# ATDevBoard.net
KiCad netlist of a schematic drawn in EAGLE
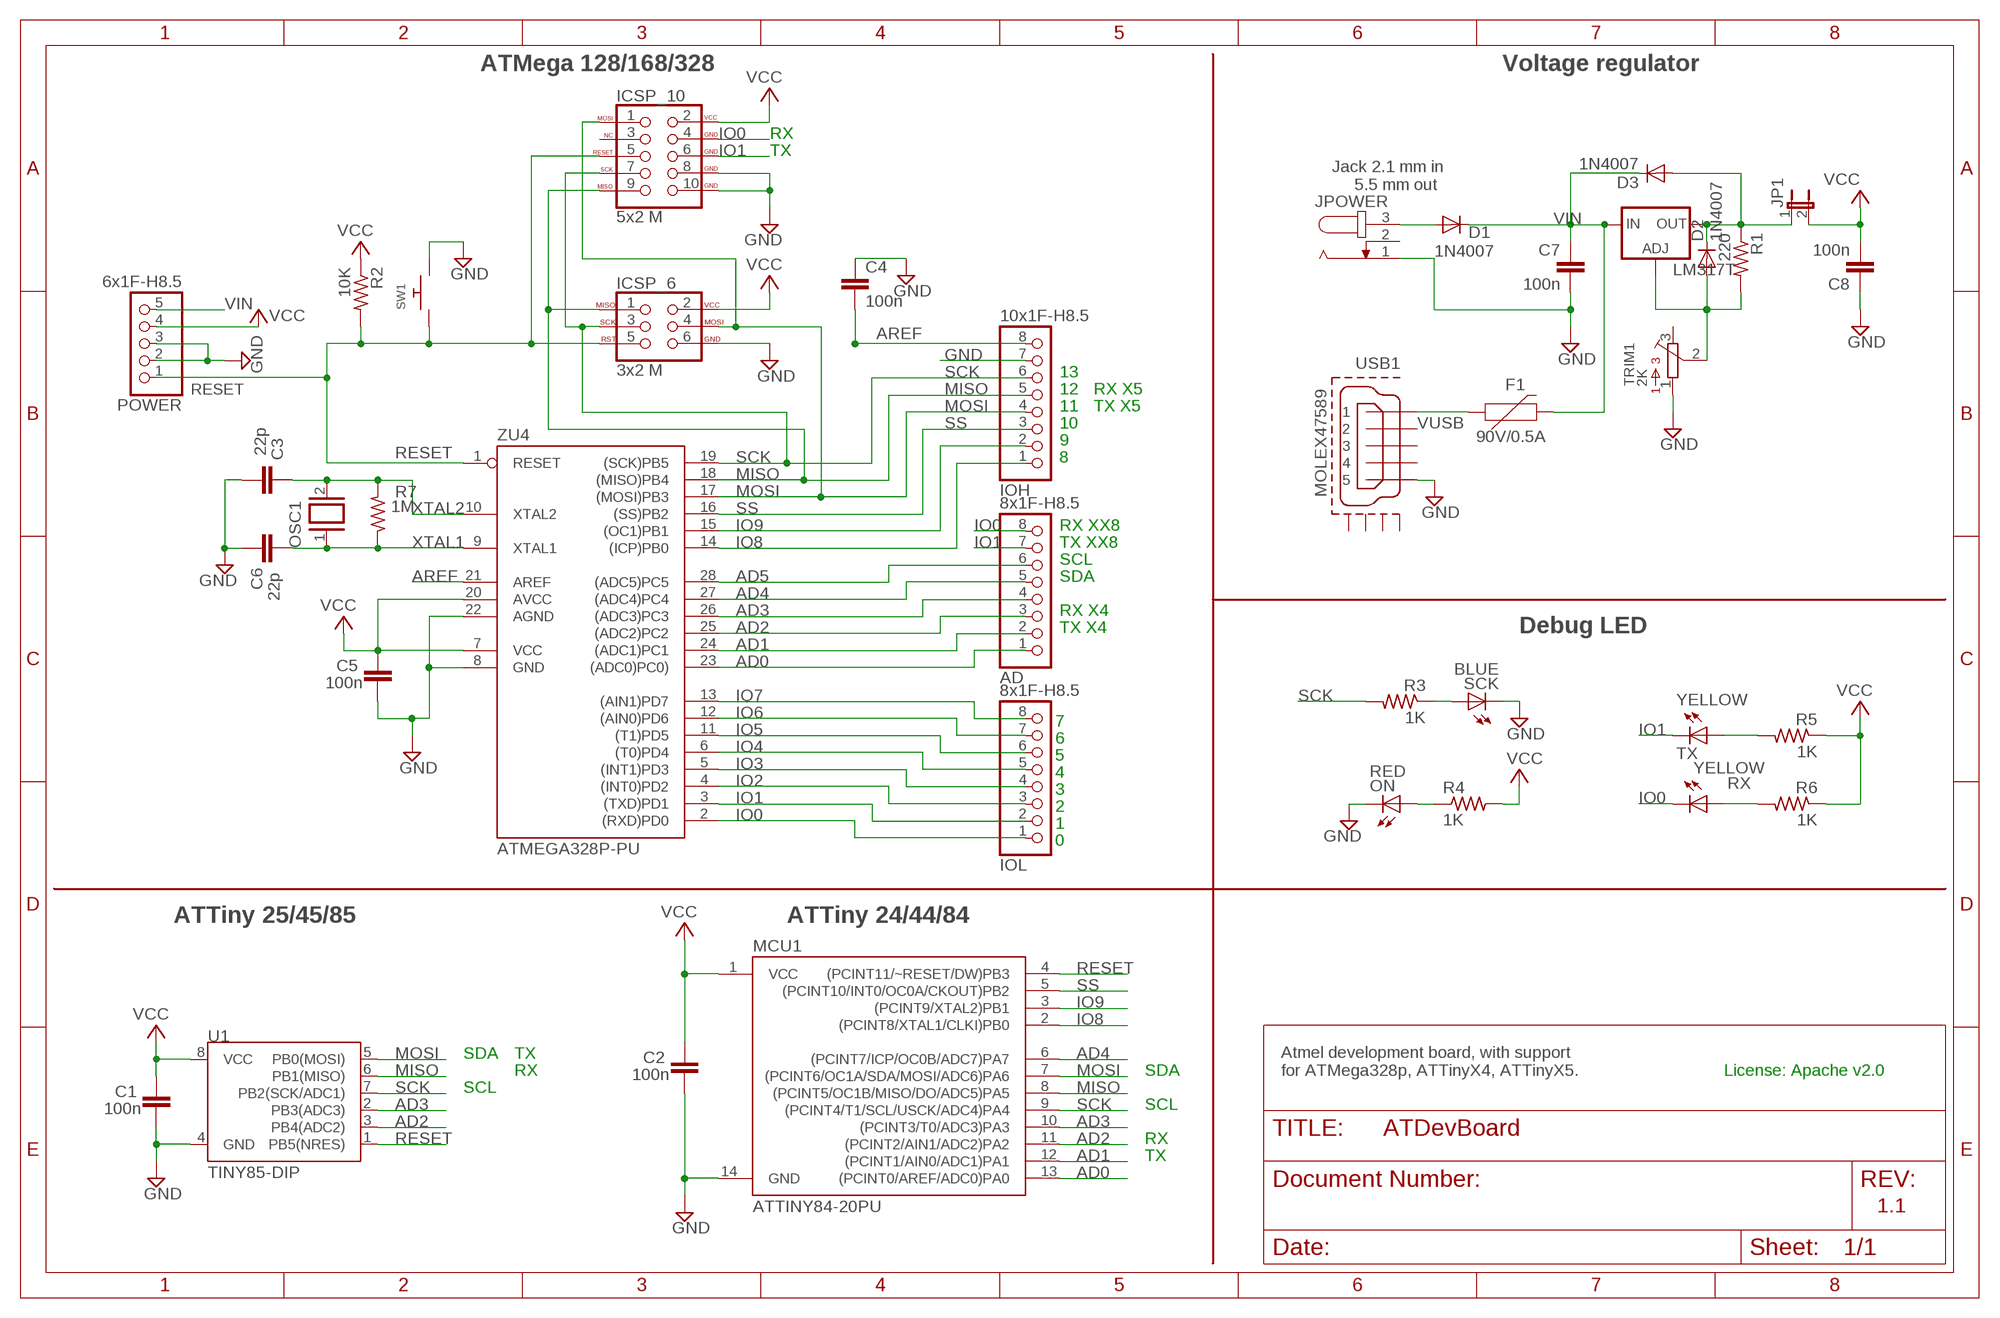
[diagram p0: schematic, sheet 1]

(export (version "E")
  (design (tool "Eeschema 10.0.6"))
  (components
    (comp (ref "AD")
      (value "8x1F-H8.5")
      (footprint "eagle-import:1X08")
      (libsource (lib "eagle-import") (part "PINHD-1X8"))
    )
    (comp (ref "C1")
      (value "100n")
      (footprint "eagle-import:C050-024X044")
      (libsource (lib "eagle-import") (part "C-EU050-024X044"))
    )
    (comp (ref "C2")
      (value "100n")
      (footprint "eagle-import:C050-024X044")
      (libsource (lib "eagle-import") (part "C-EU050-024X044"))
    )
    (comp (ref "C3")
      (value "22p")
      (footprint "eagle-import:C050-024X044")
      (libsource (lib "eagle-import") (part "C-EU050-024X044"))
    )
    (comp (ref "C4")
      (value "100n")
      (footprint "eagle-import:C050-024X044")
      (libsource (lib "eagle-import") (part "C-EU050-024X044"))
    )
    (comp (ref "C5")
      (value "100n")
      (footprint "eagle-import:C050-024X044")
      (libsource (lib "eagle-import") (part "C-EU050-024X044"))
    )
    (comp (ref "C6")
      (value "22p")
      (footprint "eagle-import:C050-024X044")
      (libsource (lib "eagle-import") (part "C-EU050-024X044"))
    )
    (comp (ref "C7")
      (value "100n")
      (footprint "eagle-import:C050-024X044")
      (libsource (lib "eagle-import") (part "rcl_C-EU050-024X044"))
    )
    (comp (ref "C8")
      (value "100n")
      (footprint "eagle-import:C050-024X044")
      (libsource (lib "eagle-import") (part "rcl_C-EU050-024X044"))
    )
    (comp (ref "D1")
      (value "1N4007")
      (footprint "eagle-import:DO41-10")
      (libsource (lib "eagle-import") (part "1N4004"))
    )
    (comp (ref "D2")
      (value "1N4007")
      (footprint "eagle-import:DO41-10")
      (libsource (lib "eagle-import") (part "1N4004"))
    )
    (comp (ref "D3")
      (value "1N4007")
      (footprint "eagle-import:DO41-10")
      (libsource (lib "eagle-import") (part "1N4004"))
    )
    (comp (ref "F1")
      (value "90V/0.5A")
      (footprint "eagle-import:PTH")
      (libsource (lib "eagle-import") (part "PPTC_PTH"))
    )
    (comp (ref "ICSP_6")
      (value "3x2 M")
      (footprint "eagle-import:2X3")
      (libsource (lib "eagle-import") (part "AVR_SPI_PROG_3X2PTH"))
    )
    (comp (ref "ICSP_10")
      (value "5x2 M")
      (footprint "eagle-import:2X5-SHROUDED")
      (libsource (lib "eagle-import") (part "AVR_SPI_PROG_5X2PTH2"))
    )
    (comp (ref "IOH")
      (value "10x1F-H8.5")
      (footprint "eagle-import:1X08")
      (libsource (lib "eagle-import") (part "PINHD-1X8"))
    )
    (comp (ref "IOL")
      (value "8x1F-H8.5")
      (footprint "eagle-import:1X08")
      (libsource (lib "eagle-import") (part "PINHD-1X8"))
    )
    (comp (ref "JP1")
      (value "JP1E")
      (footprint "eagle-import:JP1")
      (libsource (lib "eagle-import") (part "JP1E"))
    )
    (comp (ref "JPOWER")
      (value "JACK-PLUG0")
      (footprint "eagle-import:SPC4077")
      (libsource (lib "eagle-import") (part "JACK-PLUG0"))
    )
    (comp (ref "LM317T")
      (value "LM317TS")
      (footprint "eagle-import:317TS")
      (libsource (lib "eagle-import") (part "LM317TS"))
    )
    (comp (ref "MCU1")
      (value "ATTINY84-20PU")
      (footprint "eagle-import:DIL14")
      (libsource (lib "eagle-import") (part "ATTINY84ATTINY84-20PU"))
    )
    (comp (ref "ON")
      (value "RED")
      (footprint "eagle-import:CHIPLED_1206")
      (libsource (lib "eagle-import") (part "LEDCHIPLED_1206"))
    )
    (comp (ref "OSC1")
      (value "XTAL/S")
      (footprint "eagle-import:QS")
      (libsource (lib "eagle-import") (part "XTAL/S"))
    )
    (comp (ref "POWER")
      (value "6x1F-H8.5")
      (footprint "eagle-import:1X05")
      (libsource (lib "eagle-import") (part "PINHD-1X5"))
    )
    (comp (ref "R1")
      (value "220")
      (footprint "eagle-import:0204_7")
      (libsource (lib "eagle-import") (part "R-US_0204/7"))
    )
    (comp (ref "R2")
      (value "10K")
      (footprint "eagle-import:0309_12")
      (libsource (lib "eagle-import") (part "R-US_0309/12"))
    )
    (comp (ref "R3")
      (value "1K")
      (footprint "eagle-import:0207_10")
      (libsource (lib "eagle-import") (part "R-US_0207/10"))
    )
    (comp (ref "R4")
      (value "1K")
      (footprint "eagle-import:0207_10")
      (libsource (lib "eagle-import") (part "R-US_0207/10"))
    )
    (comp (ref "R5")
      (value "1K")
      (footprint "eagle-import:0207_10")
      (libsource (lib "eagle-import") (part "R-US_0207/10"))
    )
    (comp (ref "R6")
      (value "1K")
      (footprint "eagle-import:0207_10")
      (libsource (lib "eagle-import") (part "R-US_0207/10"))
    )
    (comp (ref "R7")
      (value "1M")
      (footprint "eagle-import:0309_12")
      (libsource (lib "eagle-import") (part "R-US_0309/12"))
    )
    (comp (ref "RX")
      (value "YELLOW")
      (footprint "eagle-import:CHIPLED_1206")
      (libsource (lib "eagle-import") (part "LEDCHIPLED_1206"))
    )
    (comp (ref "SCK")
      (value "BLUE")
      (footprint "eagle-import:CHIPLED_1206")
      (libsource (lib "eagle-import") (part "LEDCHIPLED_1206"))
    )
    (comp (ref "SW1")
      (value "SWITCH_PUSHBUTTONEVQ-PE")
      (footprint "eagle-import:TACT_PANA-EVQ")
      (libsource (lib "eagle-import") (part "SWITCH_PUSHBUTTONEVQ-PE"))
    )
    (comp (ref "TRIM1")
      (value "2K")
      (footprint "eagle-import:3362R")
      (libsource (lib "eagle-import") (part "3362R"))
    )
    (comp (ref "TX")
      (value "YELLOW")
      (footprint "eagle-import:CHIPLED_1206")
      (libsource (lib "eagle-import") (part "LEDCHIPLED_1206"))
    )
    (comp (ref "U1")
      (value "TINY85-DIP")
      (footprint "eagle-import:DIP08")
      (libsource (lib "eagle-import") (part "ATTINY45TINY85-20-DIP"))
    )
    (comp (ref "USB1")
      (value "MOLEX47589")
      (footprint "eagle-import:47589-0001")
      (libsource (lib "eagle-import") (part "MICRO-USB-RECEPTACLE47589-0001"))
    )
    (comp (ref "ZU4")
      (value "ATMEGA328P-PU")
      (footprint "eagle-import:DIL28-3")
      (libsource (lib "eagle-import") (part "ATMEGA328P-PU"))
    )
  )
  (nets
    (net (code "1") (name "/AD0") (class "Default")
      (node (ref "AD") (pin "1") (pinfunction "1_1") (pintype "passive"))
      (node (ref "MCU1") (pin "13") (pinfunction "(PCINT0/AREF/ADC0)PA0_13") (pintype "bidirectional"))
      (node (ref "ZU4") (pin "23") (pinfunction "(ADC0)PC0)_23") (pintype "bidirectional"))
    )
    (net (code "2") (name "/AD1") (class "Default")
      (node (ref "AD") (pin "2") (pinfunction "2_2") (pintype "passive"))
      (node (ref "MCU1") (pin "12") (pinfunction "(PCINT1/AIN0/ADC1)PA1_12") (pintype "bidirectional"))
      (node (ref "ZU4") (pin "24") (pinfunction "(ADC1)PC1_24") (pintype "bidirectional"))
    )
    (net (code "3") (name "/AD2") (class "Default")
      (node (ref "AD") (pin "3") (pinfunction "3_3") (pintype "passive"))
      (node (ref "MCU1") (pin "11") (pinfunction "(PCINT2/AIN1/ADC2)PA2_11") (pintype "bidirectional"))
      (node (ref "U1") (pin "3") (pinfunction "PB4(ADC2)_3") (pintype "bidirectional"))
      (node (ref "ZU4") (pin "25") (pinfunction "(ADC2)PC2_25") (pintype "bidirectional"))
    )
    (net (code "4") (name "/AD3") (class "Default")
      (node (ref "AD") (pin "4") (pinfunction "4_4") (pintype "passive"))
      (node (ref "MCU1") (pin "10") (pinfunction "(PCINT3/T0/ADC3)PA3_10") (pintype "bidirectional"))
      (node (ref "U1") (pin "2") (pinfunction "PB3(ADC3)_2") (pintype "bidirectional"))
      (node (ref "ZU4") (pin "26") (pinfunction "(ADC3)PC3_26") (pintype "bidirectional"))
    )
    (net (code "5") (name "/AD4") (class "Default")
      (node (ref "AD") (pin "5") (pinfunction "5_5") (pintype "passive"))
      (node (ref "MCU1") (pin "6") (pinfunction "(PCINT7/ICP/OC0B/ADC7)PA7_6") (pintype "bidirectional"))
      (node (ref "ZU4") (pin "27") (pinfunction "(ADC4)PC4_27") (pintype "bidirectional"))
    )
    (net (code "6") (name "/AD5") (class "Default")
      (node (ref "AD") (pin "6") (pinfunction "6_6") (pintype "passive"))
      (node (ref "ZU4") (pin "28") (pinfunction "(ADC5)PC5_28") (pintype "bidirectional"))
    )
    (net (code "7") (name "/AREF") (class "Default")
      (node (ref "C4") (pin "2") (pinfunction "2_2") (pintype "passive"))
      (node (ref "IOH") (pin "8") (pinfunction "8_8") (pintype "passive"))
      (node (ref "ZU4") (pin "21") (pinfunction "AREF_21") (pintype "passive"))
    )
    (net (code "8") (name "/IO0") (class "Default")
      (node (ref "AD") (pin "8") (pinfunction "8_8") (pintype "passive"))
      (node (ref "ICSP_10") (pin "4") (pinfunction "GND_4") (pintype "power_in"))
      (node (ref "IOL") (pin "1") (pinfunction "1_1") (pintype "passive"))
      (node (ref "RX") (pin "C") (pinfunction "C_C") (pintype "passive"))
      (node (ref "ZU4") (pin "2") (pinfunction "(RXD)PD0_2") (pintype "bidirectional"))
    )
    (net (code "9") (name "/IO1") (class "Default")
      (node (ref "AD") (pin "7") (pinfunction "7_7") (pintype "passive"))
      (node (ref "ICSP_10") (pin "6") (pinfunction "GND_6") (pintype "power_in"))
      (node (ref "IOL") (pin "2") (pinfunction "2_2") (pintype "passive"))
      (node (ref "TX") (pin "C") (pinfunction "C_C") (pintype "passive"))
      (node (ref "ZU4") (pin "3") (pinfunction "(TXD)PD1_3") (pintype "bidirectional"))
    )
    (net (code "10") (name "/IO2") (class "Default")
      (node (ref "IOL") (pin "3") (pinfunction "3_3") (pintype "passive"))
      (node (ref "ZU4") (pin "4") (pinfunction "(INT0)PD2_4") (pintype "bidirectional"))
    )
    (net (code "11") (name "/IO3") (class "Default")
      (node (ref "IOL") (pin "4") (pinfunction "4_4") (pintype "passive"))
      (node (ref "ZU4") (pin "5") (pinfunction "(INT1)PD3_5") (pintype "bidirectional"))
    )
    (net (code "12") (name "/IO4") (class "Default")
      (node (ref "IOL") (pin "5") (pinfunction "5_5") (pintype "passive"))
      (node (ref "ZU4") (pin "6") (pinfunction "(T0)PD4_6") (pintype "bidirectional"))
    )
    (net (code "13") (name "/IO5") (class "Default")
      (node (ref "IOL") (pin "6") (pinfunction "6_6") (pintype "passive"))
      (node (ref "ZU4") (pin "11") (pinfunction "(T1)PD5_11") (pintype "bidirectional"))
    )
    (net (code "14") (name "/IO6") (class "Default")
      (node (ref "IOL") (pin "7") (pinfunction "7_7") (pintype "passive"))
      (node (ref "ZU4") (pin "12") (pinfunction "(AIN0)PD6_12") (pintype "bidirectional"))
    )
    (net (code "15") (name "/IO7") (class "Default")
      (node (ref "IOL") (pin "8") (pinfunction "8_8") (pintype "passive"))
      (node (ref "ZU4") (pin "13") (pinfunction "(AIN1)PD7_13") (pintype "bidirectional"))
    )
    (net (code "16") (name "/IO8") (class "Default")
      (node (ref "IOH") (pin "1") (pinfunction "1_1") (pintype "passive"))
      (node (ref "MCU1") (pin "2") (pinfunction "(PCINT8/XTAL1/CLKI)PB0_2") (pintype "bidirectional"))
      (node (ref "ZU4") (pin "14") (pinfunction "(ICP)PB0_14") (pintype "bidirectional"))
    )
    (net (code "17") (name "/IO9") (class "Default")
      (node (ref "IOH") (pin "2") (pinfunction "2_2") (pintype "passive"))
      (node (ref "MCU1") (pin "3") (pinfunction "(PCINT9/XTAL2)PB1_3") (pintype "bidirectional"))
      (node (ref "ZU4") (pin "15") (pinfunction "(OC1)PB1_15") (pintype "bidirectional"))
    )
    (net (code "18") (name "/MISO") (class "Default")
      (node (ref "ICSP_10") (pin "9") (pinfunction "MISO_9") (pintype "passive"))
      (node (ref "ICSP_6") (pin "1") (pinfunction "1_1") (pintype "passive"))
      (node (ref "IOH") (pin "5") (pinfunction "5_5") (pintype "passive"))
      (node (ref "MCU1") (pin "8") (pinfunction "(PCINT5/OC1B/MISO/DO/ADC5)PA5_8") (pintype "bidirectional"))
      (node (ref "U1") (pin "6") (pinfunction "PB1(MISO)_6") (pintype "bidirectional"))
      (node (ref "ZU4") (pin "18") (pinfunction "(MISO)PB4_18") (pintype "bidirectional"))
    )
    (net (code "19") (name "/MOSI") (class "Default")
      (node (ref "ICSP_10") (pin "1") (pinfunction "MOSI_1") (pintype "passive"))
      (node (ref "ICSP_6") (pin "4") (pinfunction "4_4") (pintype "passive"))
      (node (ref "IOH") (pin "4") (pinfunction "4_4") (pintype "passive"))
      (node (ref "MCU1") (pin "7") (pinfunction "(PCINT6/OC1A/SDA/MOSI/ADC6)PA6_7") (pintype "bidirectional"))
      (node (ref "U1") (pin "5") (pinfunction "PB0(MOSI)_5") (pintype "bidirectional"))
      (node (ref "ZU4") (pin "17") (pinfunction "(MOSI)PB3_17") (pintype "bidirectional"))
    )
    (net (code "20") (name "/RESET") (class "Default")
      (node (ref "ICSP_10") (pin "5") (pinfunction "RESET_5") (pintype "passive"))
      (node (ref "ICSP_6") (pin "5") (pinfunction "5_5") (pintype "passive"))
      (node (ref "MCU1") (pin "4") (pinfunction "(PCINT11/~{RESET/DW})PB3_4") (pintype "bidirectional"))
      (node (ref "POWER") (pin "1") (pinfunction "1_1") (pintype "passive"))
      (node (ref "R2") (pin "2") (pinfunction "2_2") (pintype "passive"))
      (node (ref "SW1") (pin "P$1") (pinfunction "P$1_P$1") (pintype "passive"))
      (node (ref "U1") (pin "1") (pinfunction "PB5(NRES)_1") (pintype "bidirectional"))
      (node (ref "ZU4") (pin "1") (pinfunction "RESET_1") (pintype "input"))
    )
    (net (code "21") (name "/SCK") (class "Default")
      (node (ref "ICSP_10") (pin "7") (pinfunction "SCK_7") (pintype "passive"))
      (node (ref "ICSP_6") (pin "3") (pinfunction "3_3") (pintype "passive"))
      (node (ref "IOH") (pin "6") (pinfunction "6_6") (pintype "passive"))
      (node (ref "MCU1") (pin "9") (pinfunction "(PCINT4/T1/SCL/USCK/ADC4)PA4_9") (pintype "bidirectional"))
      (node (ref "R3") (pin "2") (pinfunction "2_2") (pintype "passive"))
      (node (ref "U1") (pin "7") (pinfunction "PB2(SCK/ADC1)_7") (pintype "bidirectional"))
      (node (ref "ZU4") (pin "19") (pinfunction "(SCK)PB5_19") (pintype "bidirectional"))
    )
    (net (code "22") (name "/SS") (class "Default")
      (node (ref "IOH") (pin "3") (pinfunction "3_3") (pintype "passive"))
      (node (ref "MCU1") (pin "5") (pinfunction "(PCINT10/INT0/OC0A/CKOUT)PB2_5") (pintype "bidirectional"))
      (node (ref "ZU4") (pin "16") (pinfunction "(SS)PB2_16") (pintype "bidirectional"))
    )
    (net (code "23") (name "/VIN") (class "Default")
      (node (ref "C7") (pin "2") (pinfunction "2_2") (pintype "passive"))
      (node (ref "D1") (pin "C") (pinfunction "C_C") (pintype "passive"))
      (node (ref "D3") (pin "C") (pinfunction "C_C") (pintype "passive"))
      (node (ref "F1") (pin "P$2") (pinfunction "2_P$2") (pintype "bidirectional"))
      (node (ref "LM317T") (pin "3") (pinfunction "IN_3") (pintype "input"))
      (node (ref "POWER") (pin "5") (pinfunction "5_5") (pintype "passive"))
    )
    (net (code "24") (name "/VUSB") (class "Default")
      (node (ref "F1") (pin "P$1") (pinfunction "1_P$1") (pintype "bidirectional"))
      (node (ref "USB1") (pin "1") (pinfunction "1_1") (pintype "input"))
    )
    (net (code "25") (name "/XTAL1") (class "Default")
      (node (ref "C6") (pin "1") (pinfunction "1_1") (pintype "passive"))
      (node (ref "OSC1") (pin "1") (pinfunction "1_1") (pintype "passive"))
      (node (ref "R7") (pin "1") (pinfunction "1_1") (pintype "passive"))
      (node (ref "ZU4") (pin "9") (pinfunction "XTAL1_9") (pintype "bidirectional"))
    )
    (net (code "26") (name "/XTAL2") (class "Default")
      (node (ref "C3") (pin "2") (pinfunction "2_2") (pintype "passive"))
      (node (ref "OSC1") (pin "2") (pinfunction "2_2") (pintype "passive"))
      (node (ref "R7") (pin "2") (pinfunction "2_2") (pintype "passive"))
      (node (ref "ZU4") (pin "10") (pinfunction "XTAL2_10") (pintype "bidirectional"))
    )
    (net (code "27") (name "GND") (class "Default")
      (node (ref "C1") (pin "1") (pinfunction "1_1") (pintype "passive"))
      (node (ref "C2") (pin "1") (pinfunction "1_1") (pintype "passive"))
      (node (ref "C3") (pin "1") (pinfunction "1_1") (pintype "passive"))
      (node (ref "C4") (pin "1") (pinfunction "1_1") (pintype "passive"))
      (node (ref "C5") (pin "1") (pinfunction "1_1") (pintype "passive"))
      (node (ref "C6") (pin "2") (pinfunction "2_2") (pintype "passive"))
      (node (ref "C7") (pin "1") (pinfunction "1_1") (pintype "passive"))
      (node (ref "C8") (pin "1") (pinfunction "1_1") (pintype "passive"))
      (node (ref "ICSP_10") (pin "10") (pinfunction "GND_10") (pintype "power_in"))
      (node (ref "ICSP_10") (pin "8") (pinfunction "GND_8") (pintype "power_in"))
      (node (ref "ICSP_6") (pin "6") (pinfunction "6_6") (pintype "passive"))
      (node (ref "IOH") (pin "7") (pinfunction "7_7") (pintype "passive"))
      (node (ref "JPOWER") (pin "1") (pinfunction "1_1") (pintype "passive"))
      (node (ref "MCU1") (pin "14") (pinfunction "GND_14") (pintype "bidirectional"))
      (node (ref "ON") (pin "C") (pinfunction "C_C") (pintype "passive"))
      (node (ref "POWER") (pin "2") (pinfunction "2_2") (pintype "passive"))
      (node (ref "POWER") (pin "3") (pinfunction "3_3") (pintype "passive"))
      (node (ref "SCK") (pin "C") (pinfunction "C_C") (pintype "passive"))
      (node (ref "SW1") (pin "P$2") (pinfunction "P$2_P$2") (pintype "passive"))
      (node (ref "TRIM1") (pin "1") (pinfunction "1_1") (pintype "passive"))
      (node (ref "U1") (pin "4") (pinfunction "GND_4") (pintype "bidirectional"))
      (node (ref "USB1") (pin "5") (pinfunction "5_5") (pintype "input"))
      (node (ref "ZU4") (pin "22") (pinfunction "AGND_22") (pintype "power_in"))
      (node (ref "ZU4") (pin "8") (pinfunction "GND_8") (pintype "power_in"))
    )
    (net (code "28") (name "Net-(D1-PadA)") (class "Default")
      (node (ref "D1") (pin "A") (pinfunction "A_A") (pintype "passive"))
      (node (ref "JPOWER") (pin "3") (pinfunction "3_3") (pintype "passive"))
    )
    (net (code "29") (name "Net-(LM317T-ADJ)") (class "Default")
      (node (ref "D2") (pin "A") (pinfunction "A_A") (pintype "passive"))
      (node (ref "LM317T") (pin "1") (pinfunction "ADJ_1") (pintype "input"))
      (node (ref "R1") (pin "2") (pinfunction "2_2") (pintype "passive"))
      (node (ref "TRIM1") (pin "2") (pinfunction "2_2") (pintype "passive"))
    )
    (net (code "30") (name "Net-(LM317T-OUT)") (class "Default")
      (node (ref "D2") (pin "C") (pinfunction "C_C") (pintype "passive"))
      (node (ref "D3") (pin "A") (pinfunction "A_A") (pintype "passive"))
      (node (ref "JP1") (pin "1") (pinfunction "1_1") (pintype "passive"))
      (node (ref "LM317T") (pin "2") (pinfunction "OUT_2") (pintype "passive"))
      (node (ref "R1") (pin "1") (pinfunction "1_1") (pintype "passive"))
    )
    (net (code "31") (name "Net-(ON-PadA)") (class "Default")
      (node (ref "ON") (pin "A") (pinfunction "A_A") (pintype "passive"))
      (node (ref "R4") (pin "1") (pinfunction "1_1") (pintype "passive"))
    )
    (net (code "32") (name "Net-(R3-Pad1)") (class "Default")
      (node (ref "R3") (pin "1") (pinfunction "1_1") (pintype "passive"))
      (node (ref "SCK") (pin "A") (pinfunction "A_A") (pintype "passive"))
    )
    (net (code "33") (name "Net-(R5-Pad2)") (class "Default")
      (node (ref "R5") (pin "2") (pinfunction "2_2") (pintype "passive"))
      (node (ref "TX") (pin "A") (pinfunction "A_A") (pintype "passive"))
    )
    (net (code "34") (name "Net-(R6-Pad2)") (class "Default")
      (node (ref "R6") (pin "2") (pinfunction "2_2") (pintype "passive"))
      (node (ref "RX") (pin "A") (pinfunction "A_A") (pintype "passive"))
    )
    (net (code "35") (name "VCC") (class "Default")
      (node (ref "C1") (pin "2") (pinfunction "2_2") (pintype "passive"))
      (node (ref "C2") (pin "2") (pinfunction "2_2") (pintype "passive"))
      (node (ref "C5") (pin "2") (pinfunction "2_2") (pintype "passive"))
      (node (ref "C8") (pin "2") (pinfunction "2_2") (pintype "passive"))
      (node (ref "ICSP_10") (pin "2") (pinfunction "VCC_2") (pintype "power_in"))
      (node (ref "ICSP_6") (pin "2") (pinfunction "2_2") (pintype "passive"))
      (node (ref "JP1") (pin "2") (pinfunction "2_2") (pintype "passive"))
      (node (ref "MCU1") (pin "1") (pinfunction "VCC_1") (pintype "bidirectional"))
      (node (ref "POWER") (pin "4") (pinfunction "4_4") (pintype "passive"))
      (node (ref "R2") (pin "1") (pinfunction "1_1") (pintype "passive"))
      (node (ref "R4") (pin "2") (pinfunction "2_2") (pintype "passive"))
      (node (ref "R5") (pin "1") (pinfunction "1_1") (pintype "passive"))
      (node (ref "R6") (pin "1") (pinfunction "1_1") (pintype "passive"))
      (node (ref "U1") (pin "8") (pinfunction "VCC_8") (pintype "bidirectional"))
      (node (ref "ZU4") (pin "20") (pinfunction "AVCC_20") (pintype "power_in"))
      (node (ref "ZU4") (pin "7") (pinfunction "VCC_7") (pintype "power_in"))
    )
    (net (code "36") (name "unconnected-(ICSP_10-NC-Pad3)") (class "Default")
      (node (ref "ICSP_10") (pin "3") (pinfunction "NC_3") (pintype "no_connect"))
    )
    (net (code "37") (name "unconnected-(JPOWER-Pad2)") (class "Default")
      (node (ref "JPOWER") (pin "2") (pinfunction "2_2") (pintype "passive"))
    )
    (net (code "38") (name "unconnected-(TRIM1-Pad3)") (class "Default")
      (node (ref "TRIM1") (pin "3") (pinfunction "3_3") (pintype "passive"))
    )
    (net (code "39") (name "unconnected-(USB1-GND1-PadCASING1)") (class "Default")
      (node (ref "USB1") (pin "CASING1") (pinfunction "GND1_CASING1") (pintype "bidirectional"))
    )
    (net (code "40") (name "unconnected-(USB1-GND2-PadCASING2)") (class "Default")
      (node (ref "USB1") (pin "CASING2") (pinfunction "GND2_CASING2") (pintype "bidirectional"))
    )
    (net (code "41") (name "unconnected-(USB1-GND3-PadCASING3)") (class "Default")
      (node (ref "USB1") (pin "CASING3") (pinfunction "GND3_CASING3") (pintype "bidirectional"))
    )
    (net (code "42") (name "unconnected-(USB1-GND4-PadCASING4)") (class "Default")
      (node (ref "USB1") (pin "CASING4") (pinfunction "GND4_CASING4") (pintype "bidirectional"))
    )
    (net (code "43") (name "unconnected-(USB1-Pad2)") (class "Default")
      (node (ref "USB1") (pin "2") (pinfunction "2_2") (pintype "input"))
    )
    (net (code "44") (name "unconnected-(USB1-Pad3)") (class "Default")
      (node (ref "USB1") (pin "3") (pinfunction "3_3") (pintype "input"))
    )
    (net (code "45") (name "unconnected-(USB1-Pad4)") (class "Default")
      (node (ref "USB1") (pin "4") (pinfunction "4_4") (pintype "input"))
    )
  )
)
